# TerminalBlock.net
KiCad netlist of a schematic drawn in Altium Designer
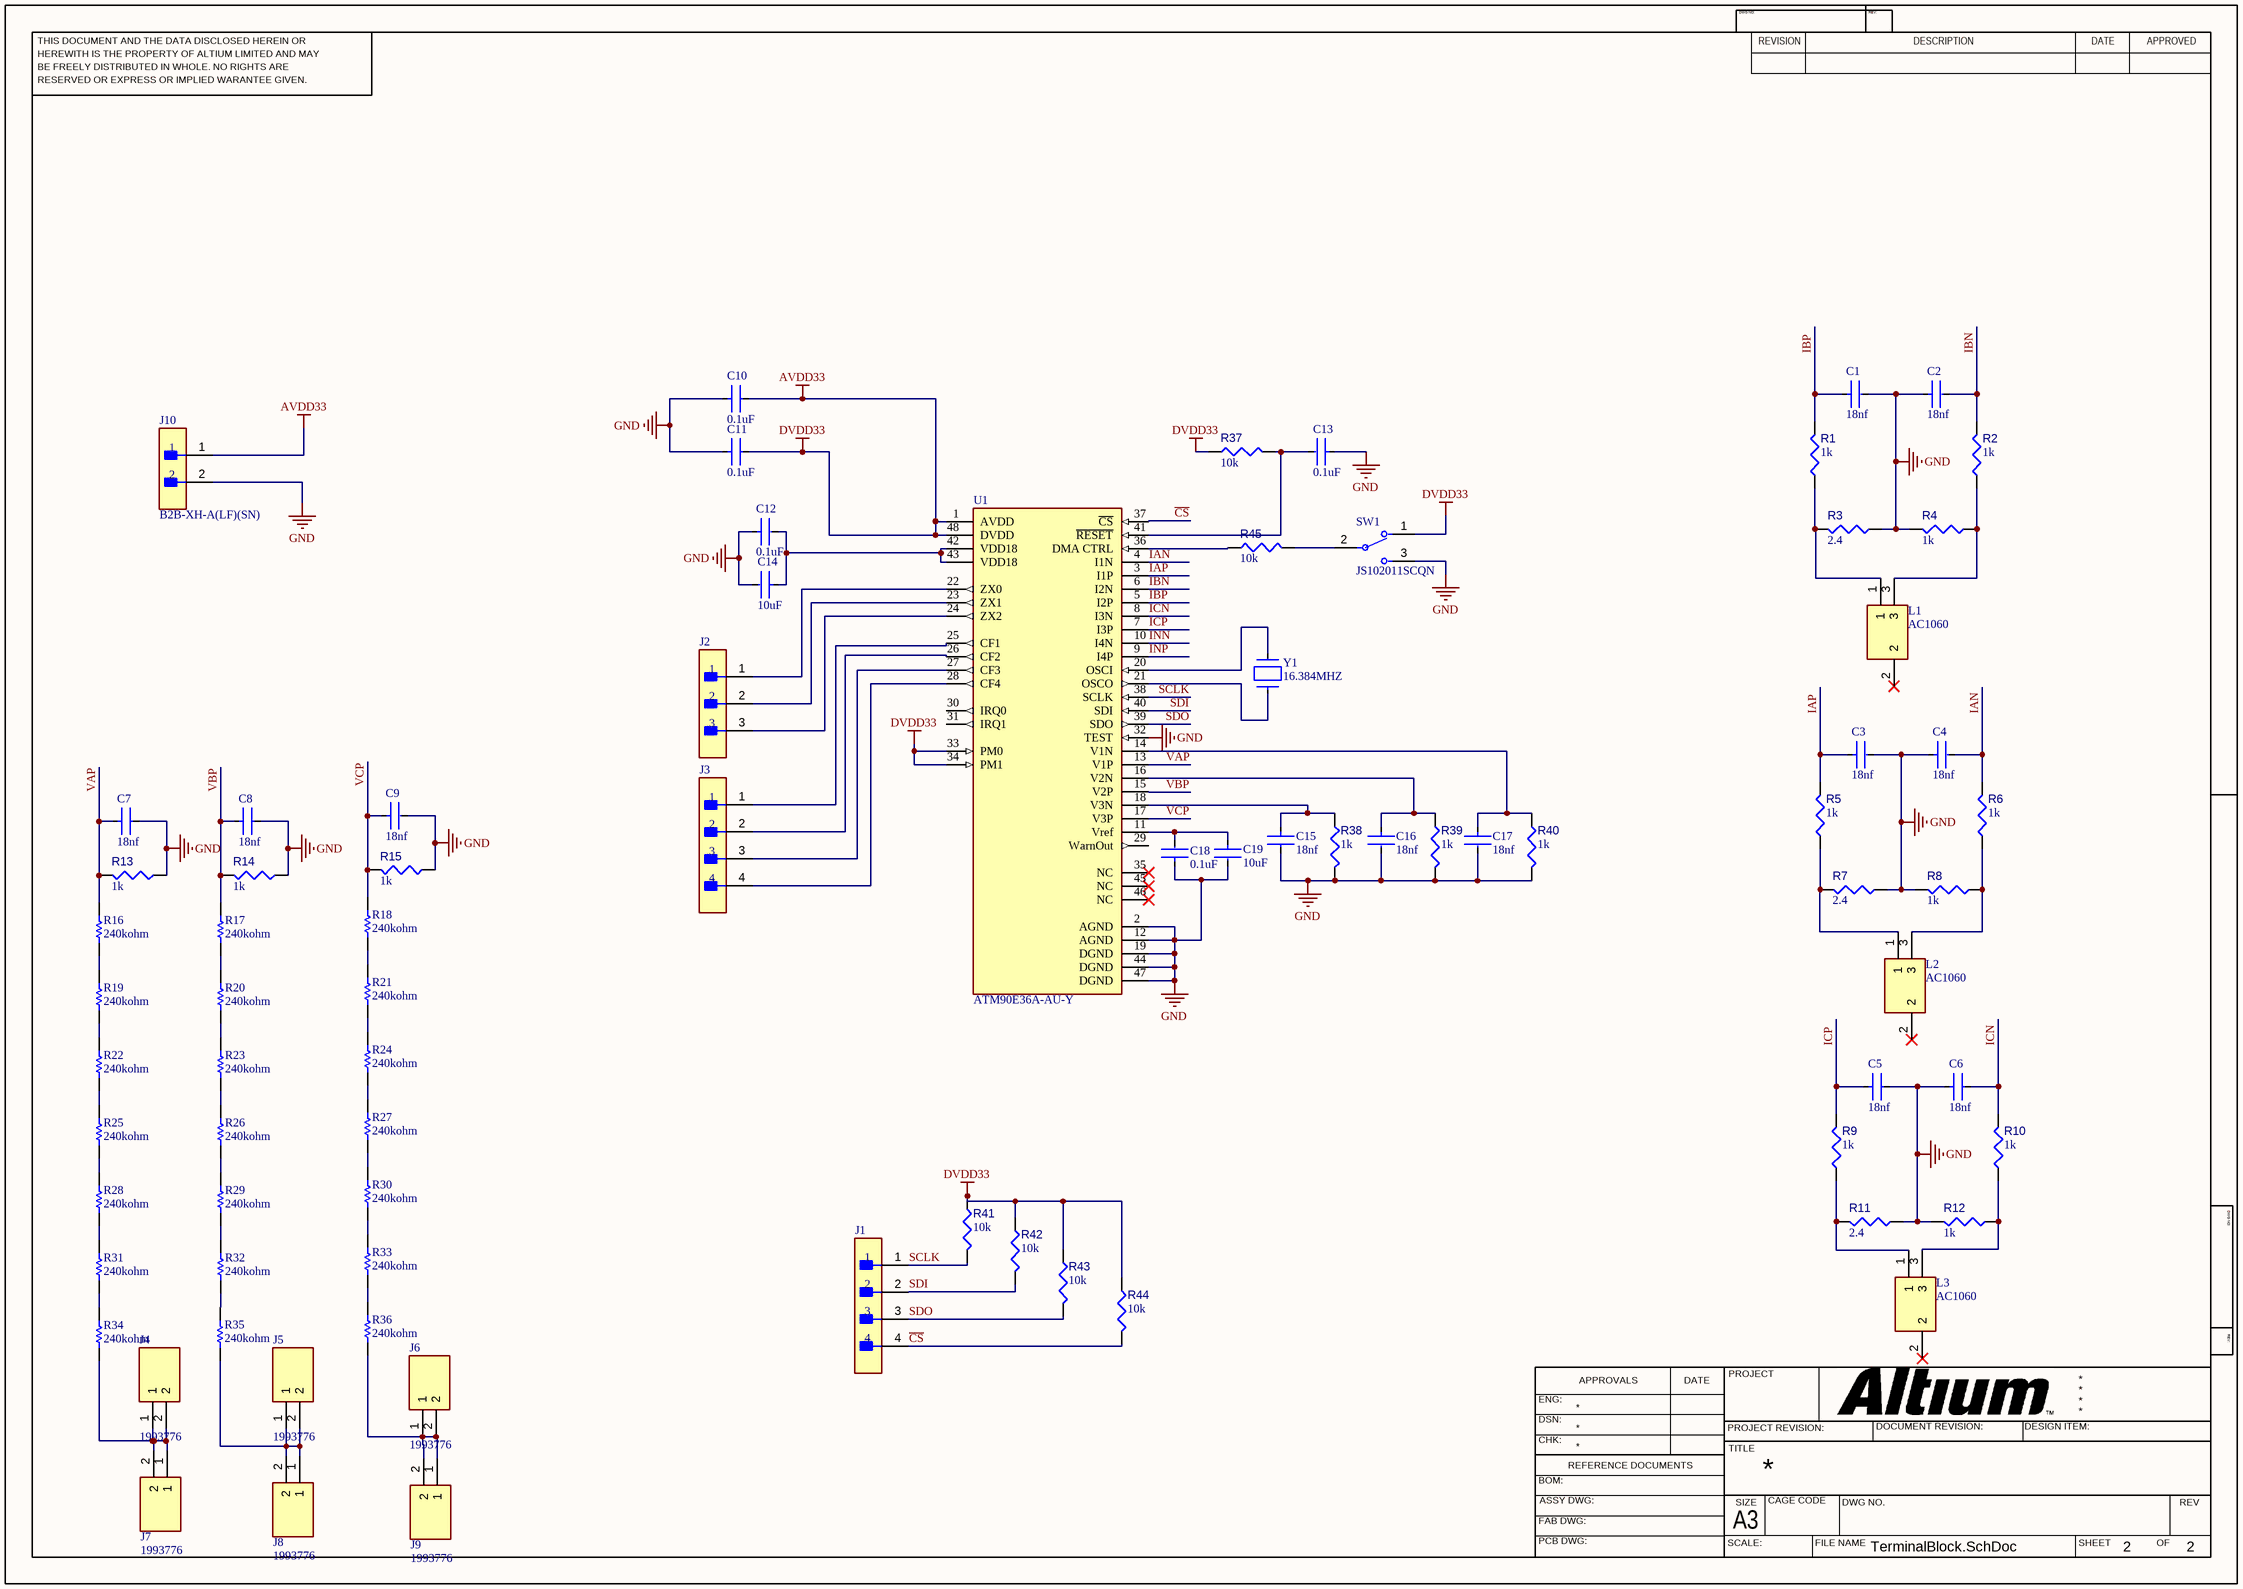
[diagram p0: TerminalBlock.SchDoc]

(export (version "E")
  (design (tool "Eeschema 10.0.6"))
  (components
    (comp (ref "C1")
      (value "18nf")
      (footprint "FP-C0603C-CF-MFG")
      (description "CAP CER 0.018UF 50V 10% X7R 0603")
      (fields
        (field (name "OCTOPART") "https://octopart.com/c0603c183k5ractu-kemet-9138582")
        (field (name "TOLERANCE") "0.1")
      )
      (libsource (lib "Altium Content Vault") (part "b4654b650e69147ec39a6b967a45e02"))
    )
    (comp (ref "C2")
      (value "18nf")
      (footprint "FP-C0603C-CF-MFG")
      (description "CAP CER 0.018UF 50V 10% X7R 0603")
      (fields
        (field (name "OCTOPART") "https://octopart.com/c0603c183k5ractu-kemet-9138582")
        (field (name "TOLERANCE") "0.1")
      )
      (libsource (lib "Altium Content Vault") (part "b4654b650e69147ec39a6b967a45e02"))
    )
    (comp (ref "C3")
      (value "18nf")
      (footprint "FP-C0603C-CF-MFG")
      (description "CAP CER 0.018UF 50V 10% X7R 0603")
      (fields
        (field (name "OCTOPART") "https://octopart.com/c0603c183k5ractu-kemet-9138582")
        (field (name "TOLERANCE") "0.1")
      )
      (libsource (lib "Altium Content Vault") (part "b4654b650e69147ec39a6b967a45e02"))
    )
    (comp (ref "C4")
      (value "18nf")
      (footprint "FP-C0603C-CF-MFG")
      (description "CAP CER 0.018UF 50V 10% X7R 0603")
      (fields
        (field (name "OCTOPART") "https://octopart.com/c0603c183k5ractu-kemet-9138582")
        (field (name "TOLERANCE") "0.1")
      )
      (libsource (lib "Altium Content Vault") (part "b4654b650e69147ec39a6b967a45e02"))
    )
    (comp (ref "C5")
      (value "18nf")
      (footprint "FP-C0603C-CF-MFG")
      (description "CAP CER 0.018UF 50V 10% X7R 0603")
      (fields
        (field (name "OCTOPART") "https://octopart.com/c0603c183k5ractu-kemet-9138582")
        (field (name "TOLERANCE") "0.1")
      )
      (libsource (lib "Altium Content Vault") (part "b4654b650e69147ec39a6b967a45e02"))
    )
    (comp (ref "C6")
      (value "18nf")
      (footprint "FP-C0603C-CF-MFG")
      (description "CAP CER 0.018UF 50V 10% X7R 0603")
      (fields
        (field (name "OCTOPART") "https://octopart.com/c0603c183k5ractu-kemet-9138582")
        (field (name "TOLERANCE") "0.1")
      )
      (libsource (lib "Altium Content Vault") (part "b4654b650e69147ec39a6b967a45e02"))
    )
    (comp (ref "C7")
      (value "18nf")
      (footprint "FP-C0603C-CF-MFG")
      (description "CAP CER 0.018UF 50V 10% X7R 0603")
      (fields
        (field (name "OCTOPART") "https://octopart.com/c0603c183k5ractu-kemet-9138582")
        (field (name "TOLERANCE") "0.1")
      )
      (libsource (lib "Altium Content Vault") (part "b4654b650e69147ec39a6b967a45e02"))
    )
    (comp (ref "C8")
      (value "18nf")
      (footprint "FP-C0603C-CF-MFG")
      (description "CAP CER 0.018UF 50V 10% X7R 0603")
      (fields
        (field (name "OCTOPART") "https://octopart.com/c0603c183k5ractu-kemet-9138582")
        (field (name "TOLERANCE") "0.1")
      )
      (libsource (lib "Altium Content Vault") (part "b4654b650e69147ec39a6b967a45e02"))
    )
    (comp (ref "C9")
      (value "18nf")
      (footprint "FP-C0603C-CF-MFG")
      (description "CAP CER 0.018UF 50V 10% X7R 0603")
      (fields
        (field (name "OCTOPART") "https://octopart.com/c0603c183k5ractu-kemet-9138582")
        (field (name "TOLERANCE") "0.1")
      )
      (libsource (lib "Altium Content Vault") (part "b4654b650e69147ec39a6b967a45e02"))
    )
    (comp (ref "C10")
      (value "0.1uF")
      (footprint "FP-C0603-CJ-MFG")
      (description "CAP CER 0.1UF 50V X7R 0603")
      (fields (field (name "MANUFACTURER PART NUMBER") "C0603X104K5RACTU") (field (name "VOLTAGE") "50V"))
      (libsource (lib "Altium Content Vault") (part "11868f565c42a9108669ba33697ecf6"))
    )
    (comp (ref "C11")
      (value "0.1uF")
      (footprint "FP-C0603-CJ-MFG")
      (description "CAP CER 0.1UF 50V X7R 0603")
      (fields (field (name "MANUFACTURER PART NUMBER") "C0603X104K5RACTU") (field (name "VOLTAGE") "50V"))
      (libsource (lib "Altium Content Vault") (part "11868f565c42a9108669ba33697ecf6"))
    )
    (comp (ref "C12")
      (value "0.1uF")
      (footprint "FP-C0603-CJ-MFG")
      (description "CAP CER 0.1UF 50V X7R 0603")
      (fields (field (name "MANUFACTURER PART NUMBER") "C0603X104K5RACTU") (field (name "VOLTAGE") "50V"))
      (libsource (lib "Altium Content Vault") (part "11868f565c42a9108669ba33697ecf6"))
    )
    (comp (ref "C13")
      (value "0.1uF")
      (footprint "FP-C0603-CJ-MFG")
      (description "CAP CER 0.1UF 50V X7R 0603")
      (fields (field (name "MANUFACTURER PART NUMBER") "C0603X104K5RACTU") (field (name "VOLTAGE") "50V"))
      (libsource (lib "Altium Content Vault") (part "11868f565c42a9108669ba33697ecf6"))
    )
    (comp (ref "C14")
      (value "10uF")
      (footprint "FP-C0603C106M9PACTU-MFG")
      (description "CAP CER 10UF 6.3V X5R 0603")
      (fields
        (field (name "MANUFACTURER PART NUMBER") "C0603C106M9PACTU")
        (field (name "MANUFACTURER") "Kemet")
      )
      (libsource (lib "Altium Content Vault") (part "b4654b650e69147ec39a6b967a45e02"))
    )
    (comp (ref "C15")
      (value "18nf")
      (footprint "FP-C0603C-CF-MFG")
      (description "CAP CER 0.018UF 50V 10% X7R 0603")
      (fields
        (field (name "OCTOPART") "https://octopart.com/c0603c183k5ractu-kemet-9138582")
        (field (name "TOLERANCE") "0.1")
      )
      (libsource (lib "Altium Content Vault") (part "b4654b650e69147ec39a6b967a45e02"))
    )
    (comp (ref "C16")
      (value "18nf")
      (footprint "FP-C0603C-CF-MFG")
      (description "CAP CER 0.018UF 50V 10% X7R 0603")
      (fields
        (field (name "OCTOPART") "https://octopart.com/c0603c183k5ractu-kemet-9138582")
        (field (name "TOLERANCE") "0.1")
      )
      (libsource (lib "Altium Content Vault") (part "b4654b650e69147ec39a6b967a45e02"))
    )
    (comp (ref "C17")
      (value "18nf")
      (footprint "FP-C0603C-CF-MFG")
      (description "CAP CER 0.018UF 50V 10% X7R 0603")
      (fields
        (field (name "OCTOPART") "https://octopart.com/c0603c183k5ractu-kemet-9138582")
        (field (name "TOLERANCE") "0.1")
      )
      (libsource (lib "Altium Content Vault") (part "b4654b650e69147ec39a6b967a45e02"))
    )
    (comp (ref "C18")
      (value "0.1uF")
      (footprint "FP-C0603-CJ-MFG")
      (description "CAP CER 0.1UF 50V X7R 0603")
      (fields (field (name "MANUFACTURER PART NUMBER") "C0603X104K5RACTU") (field (name "VOLTAGE") "50V"))
      (libsource (lib "Altium Content Vault") (part "11868f565c42a9108669ba33697ecf6"))
    )
    (comp (ref "C19")
      (value "10uF")
      (footprint "FP-C0603C106M9PACTU-MFG")
      (description "CAP CER 10UF 6.3V X5R 0603")
      (fields
        (field (name "MANUFACTURER PART NUMBER") "C0603C106M9PACTU")
        (field (name "MANUFACTURER") "Kemet")
      )
      (libsource (lib "Altium Content Vault") (part "b4654b650e69147ec39a6b967a45e02"))
    )
    (comp (ref "J1")
      (value "B4B-XH-A(LF)(SN)")
      (footprint "FP-B4B-XH-A_LF_SN-MFG")
      (description "CONN HEADER VERT 4POS 2.5MM")
      (libsource (lib "Altium Content Vault") (part "299a8cea1bdcbc3624fe62c390fa72c"))
    )
    (comp (ref "J2")
      (value "B3B-XH-A(LF)(SN)")
      (footprint "FP-B3B-XH-A_LF_SN-MFG")
      (description "CONN HEADER VERT 3POS 2.5MM")
      (libsource (lib "Altium Content Vault") (part "0d3f023dd272f625e17a2be33dea85f"))
    )
    (comp (ref "J3")
      (value "B4B-XH-A(LF)(SN)")
      (footprint "FP-B4B-XH-A_LF_SN-MFG")
      (description "CONN HEADER VERT 4POS 2.5MM")
      (libsource (lib "Altium Content Vault") (part "299a8cea1bdcbc3624fe62c390fa72c"))
    )
    (comp (ref "J4")
      (value "1993776")
      (footprint "SamacSys:1993776")
      (description "Connector")
      (fields (field (name "MOUSER PART NUMBER") "651-1993776"))
      (libsource (lib "") (part "1993776_1"))
    )
    (comp (ref "J5")
      (value "1993776")
      (footprint "SamacSys:1993776")
      (description "Connector")
      (fields (field (name "MOUSER PART NUMBER") "651-1993776"))
      (libsource (lib "") (part "1993776_1"))
    )
    (comp (ref "J6")
      (value "1993776")
      (footprint "SamacSys:1993776")
      (description "Connector")
      (fields (field (name "MOUSER PART NUMBER") "651-1993776"))
      (libsource (lib "") (part "1993776_1"))
    )
    (comp (ref "J7")
      (value "1993776")
      (footprint "SamacSys:1993776")
      (description "Connector")
      (fields (field (name "MOUSER PART NUMBER") "651-1993776"))
      (libsource (lib "*") (part "1993776"))
    )
    (comp (ref "J8")
      (value "1993776")
      (footprint "SamacSys:1993776")
      (description "Connector")
      (fields (field (name "MOUSER PART NUMBER") "651-1993776"))
      (libsource (lib "*") (part "1993776"))
    )
    (comp (ref "J9")
      (value "1993776")
      (footprint "SamacSys:1993776")
      (description "Connector")
      (fields (field (name "MOUSER PART NUMBER") "651-1993776"))
      (libsource (lib "*") (part "1993776"))
    )
    (comp (ref "J10")
      (value "B2B-XH-A(LF)(SN)")
      (footprint "FP-B2B-XH-A_LF_SN-MFG")
      (description "CONN HEADER VERT 2POS 2.5MM")
      (libsource (lib "Altium Content Vault") (part "3bc925449376181038e59eaffc5286c"))
    )
    (comp (ref "L1")
      (value "AC1060")
      (footprint "SamacSys:AC1060")
      (description "Inductor")
      (libsource (lib "*") (part "AC1060"))
    )
    (comp (ref "L2")
      (value "AC1060")
      (footprint "SamacSys:AC1060")
      (description "Inductor")
      (libsource (lib "*") (part "AC1060"))
    )
    (comp (ref "L3")
      (value "AC1060")
      (footprint "SamacSys:AC1060")
      (description "Inductor")
      (libsource (lib "*") (part "AC1060"))
    )
    (comp (ref "R1")
      (value "1k")
      (footprint "RESC1608X55X25ML10T15")
      (description "Chip Resistor, 100 KOhm, +/- 1%, 0.1 W, -55 to 155 degC, 0603 (1608 Metric)")
      (fields (field (name "TOLERANCE") "1%") (field (name "POWER") "100mW"))
      (libsource (lib "University of Moratuwa") (part "RES-2"))
    )
    (comp (ref "R2")
      (value "1k")
      (footprint "RESC1608X55X25ML10T15")
      (description "Chip Resistor, 100 KOhm, +/- 1%, 0.1 W, -55 to 155 degC, 0603 (1608 Metric)")
      (fields (field (name "TOLERANCE") "1%") (field (name "POWER") "100mW"))
      (libsource (lib "University of Moratuwa") (part "RES-2"))
    )
    (comp (ref "R3")
      (value "2.4")
      (footprint "RESC1608X55X25ML10T15")
      (description "Chip Resistor, 100 KOhm, +/- 1%, 0.1 W, -55 to 155 degC, 0603 (1608 Metric)")
      (fields (field (name "TOLERANCE") "1%") (field (name "POWER") "100mW"))
      (libsource (lib "University of Moratuwa") (part "RES-2"))
    )
    (comp (ref "R4")
      (value "1k")
      (footprint "RESC1608X55X25ML10T15")
      (description "Chip Resistor, 100 KOhm, +/- 1%, 0.1 W, -55 to 155 degC, 0603 (1608 Metric)")
      (fields (field (name "TOLERANCE") "1%") (field (name "POWER") "100mW"))
      (libsource (lib "University of Moratuwa") (part "RES-2"))
    )
    (comp (ref "R5")
      (value "1k")
      (footprint "RESC1608X55X25ML10T15")
      (description "Chip Resistor, 100 KOhm, +/- 1%, 0.1 W, -55 to 155 degC, 0603 (1608 Metric)")
      (fields (field (name "TOLERANCE") "1%") (field (name "POWER") "100mW"))
      (libsource (lib "University of Moratuwa") (part "RES-2"))
    )
    (comp (ref "R6")
      (value "1k")
      (footprint "RESC1608X55X25ML10T15")
      (description "Chip Resistor, 100 KOhm, +/- 1%, 0.1 W, -55 to 155 degC, 0603 (1608 Metric)")
      (fields (field (name "TOLERANCE") "1%") (field (name "POWER") "100mW"))
      (libsource (lib "University of Moratuwa") (part "RES-2"))
    )
    (comp (ref "R7")
      (value "2.4")
      (footprint "RESC1608X55X25ML10T15")
      (description "Chip Resistor, 100 KOhm, +/- 1%, 0.1 W, -55 to 155 degC, 0603 (1608 Metric)")
      (fields (field (name "TOLERANCE") "1%") (field (name "POWER") "100mW"))
      (libsource (lib "University of Moratuwa") (part "RES-2"))
    )
    (comp (ref "R8")
      (value "1k")
      (footprint "RESC1608X55X25ML10T15")
      (description "Chip Resistor, 100 KOhm, +/- 1%, 0.1 W, -55 to 155 degC, 0603 (1608 Metric)")
      (fields (field (name "TOLERANCE") "1%") (field (name "POWER") "100mW"))
      (libsource (lib "University of Moratuwa") (part "RES-2"))
    )
    (comp (ref "R9")
      (value "1k")
      (footprint "RESC1608X55X25ML10T15")
      (description "Chip Resistor, 100 KOhm, +/- 1%, 0.1 W, -55 to 155 degC, 0603 (1608 Metric)")
      (fields (field (name "TOLERANCE") "1%") (field (name "POWER") "100mW"))
      (libsource (lib "University of Moratuwa") (part "RES-2"))
    )
    (comp (ref "R10")
      (value "1k")
      (footprint "RESC1608X55X25ML10T15")
      (description "Chip Resistor, 100 KOhm, +/- 1%, 0.1 W, -55 to 155 degC, 0603 (1608 Metric)")
      (fields (field (name "TOLERANCE") "1%") (field (name "POWER") "100mW"))
      (libsource (lib "University of Moratuwa") (part "RES-2"))
    )
    (comp (ref "R11")
      (value "2.4")
      (footprint "RESC1608X55X25ML10T15")
      (description "Chip Resistor, 100 KOhm, +/- 1%, 0.1 W, -55 to 155 degC, 0603 (1608 Metric)")
      (fields (field (name "TOLERANCE") "1%") (field (name "POWER") "100mW"))
      (libsource (lib "University of Moratuwa") (part "RES-2"))
    )
    (comp (ref "R12")
      (value "1k")
      (footprint "RESC1608X55X25ML10T15")
      (description "Chip Resistor, 100 KOhm, +/- 1%, 0.1 W, -55 to 155 degC, 0603 (1608 Metric)")
      (fields (field (name "TOLERANCE") "1%") (field (name "POWER") "100mW"))
      (libsource (lib "University of Moratuwa") (part "RES-2"))
    )
    (comp (ref "R13")
      (value "1k")
      (footprint "RESC1608X55X25ML10T15")
      (description "Chip Resistor, 100 KOhm, +/- 1%, 0.1 W, -55 to 155 degC, 0603 (1608 Metric)")
      (fields (field (name "TOLERANCE") "1%") (field (name "POWER") "100mW"))
      (libsource (lib "University of Moratuwa") (part "RES-2"))
    )
    (comp (ref "R14")
      (value "1k")
      (footprint "RESC1608X55X25ML10T15")
      (description "Chip Resistor, 100 KOhm, +/- 1%, 0.1 W, -55 to 155 degC, 0603 (1608 Metric)")
      (fields (field (name "TOLERANCE") "1%") (field (name "POWER") "100mW"))
      (libsource (lib "University of Moratuwa") (part "RES-2"))
    )
    (comp (ref "R15")
      (value "1k")
      (footprint "RESC1608X55X25ML10T15")
      (description "Chip Resistor, 100 KOhm, +/- 1%, 0.1 W, -55 to 155 degC, 0603 (1608 Metric)")
      (fields (field (name "TOLERANCE") "1%") (field (name "POWER") "100mW"))
      (libsource (lib "University of Moratuwa") (part "RES-2"))
    )
    (comp (ref "R16")
      (value "240kohm")
      (footprint "RESC1608X55X30NL20T20")
      (fields (field (name "PART NUMBER") "ERA3AEB244V") (field (name "MANUFACTURER") "Panasonic"))
      (libsource (lib "Altium Content Vault") (part "RES"))
    )
    (comp (ref "R17")
      (value "240kohm")
      (footprint "RESC1608X55X30NL20T20")
      (fields (field (name "PART NUMBER") "ERA3AEB244V") (field (name "MANUFACTURER") "Panasonic"))
      (libsource (lib "Altium Content Vault") (part "RES"))
    )
    (comp (ref "R18")
      (value "240kohm")
      (footprint "RESC1608X55X30NL20T20")
      (fields (field (name "PART NUMBER") "ERA3AEB244V") (field (name "MANUFACTURER") "Panasonic"))
      (libsource (lib "Altium Content Vault") (part "RES"))
    )
    (comp (ref "R19")
      (value "240kohm")
      (footprint "RESC1608X55X30NL20T20")
      (fields (field (name "PART NUMBER") "ERA3AEB244V") (field (name "MANUFACTURER") "Panasonic"))
      (libsource (lib "Altium Content Vault") (part "RES"))
    )
    (comp (ref "R20")
      (value "240kohm")
      (footprint "RESC1608X55X30NL20T20")
      (fields (field (name "PART NUMBER") "ERA3AEB244V") (field (name "MANUFACTURER") "Panasonic"))
      (libsource (lib "Altium Content Vault") (part "RES"))
    )
    (comp (ref "R21")
      (value "240kohm")
      (footprint "RESC1608X55X30NL20T20")
      (fields (field (name "PART NUMBER") "ERA3AEB244V") (field (name "MANUFACTURER") "Panasonic"))
      (libsource (lib "Altium Content Vault") (part "RES"))
    )
    (comp (ref "R22")
      (value "240kohm")
      (footprint "RESC1608X55X30NL20T20")
      (fields (field (name "PART NUMBER") "ERA3AEB244V") (field (name "MANUFACTURER") "Panasonic"))
      (libsource (lib "Altium Content Vault") (part "RES"))
    )
    (comp (ref "R23")
      (value "240kohm")
      (footprint "RESC1608X55X30NL20T20")
      (fields (field (name "PART NUMBER") "ERA3AEB244V") (field (name "MANUFACTURER") "Panasonic"))
      (libsource (lib "Altium Content Vault") (part "RES"))
    )
    (comp (ref "R24")
      (value "240kohm")
      (footprint "RESC1608X55X30NL20T20")
      (fields (field (name "PART NUMBER") "ERA3AEB244V") (field (name "MANUFACTURER") "Panasonic"))
      (libsource (lib "Altium Content Vault") (part "RES"))
    )
    (comp (ref "R25")
      (value "240kohm")
      (footprint "RESC1608X55X30NL20T20")
      (fields (field (name "PART NUMBER") "ERA3AEB244V") (field (name "MANUFACTURER") "Panasonic"))
      (libsource (lib "Altium Content Vault") (part "RES"))
    )
    (comp (ref "R26")
      (value "240kohm")
      (footprint "RESC1608X55X30NL20T20")
      (fields (field (name "PART NUMBER") "ERA3AEB244V") (field (name "MANUFACTURER") "Panasonic"))
      (libsource (lib "Altium Content Vault") (part "RES"))
    )
    (comp (ref "R27")
      (value "240kohm")
      (footprint "RESC1608X55X30NL20T20")
      (fields (field (name "PART NUMBER") "ERA3AEB244V") (field (name "MANUFACTURER") "Panasonic"))
      (libsource (lib "Altium Content Vault") (part "RES"))
    )
    (comp (ref "R28")
      (value "240kohm")
      (footprint "RESC1608X55X30NL20T20")
      (fields (field (name "PART NUMBER") "ERA3AEB244V") (field (name "MANUFACTURER") "Panasonic"))
      (libsource (lib "Altium Content Vault") (part "RES"))
    )
    (comp (ref "R29")
      (value "240kohm")
      (footprint "RESC1608X55X30NL20T20")
      (fields (field (name "PART NUMBER") "ERA3AEB244V") (field (name "MANUFACTURER") "Panasonic"))
      (libsource (lib "Altium Content Vault") (part "RES"))
    )
    (comp (ref "R30")
      (value "240kohm")
      (footprint "RESC1608X55X30NL20T20")
      (fields (field (name "PART NUMBER") "ERA3AEB244V") (field (name "MANUFACTURER") "Panasonic"))
      (libsource (lib "Altium Content Vault") (part "RES"))
    )
    (comp (ref "R31")
      (value "240kohm")
      (footprint "RESC1608X55X30NL20T20")
      (fields (field (name "PART NUMBER") "ERA3AEB244V") (field (name "MANUFACTURER") "Panasonic"))
      (libsource (lib "Altium Content Vault") (part "RES"))
    )
    (comp (ref "R32")
      (value "240kohm")
      (footprint "RESC1608X55X30NL20T20")
      (fields (field (name "PART NUMBER") "ERA3AEB244V") (field (name "MANUFACTURER") "Panasonic"))
      (libsource (lib "Altium Content Vault") (part "RES"))
    )
    (comp (ref "R33")
      (value "240kohm")
      (footprint "RESC1608X55X30NL20T20")
      (fields (field (name "PART NUMBER") "ERA3AEB244V") (field (name "MANUFACTURER") "Panasonic"))
      (libsource (lib "Altium Content Vault") (part "RES"))
    )
    (comp (ref "R34")
      (value "240kohm")
      (footprint "RESC1608X55X30NL20T20")
      (fields (field (name "PART NUMBER") "ERA3AEB244V") (field (name "MANUFACTURER") "Panasonic"))
      (libsource (lib "Altium Content Vault") (part "RES"))
    )
    (comp (ref "R35")
      (value "240kohm")
      (footprint "RESC1608X55X30NL20T20")
      (fields (field (name "PART NUMBER") "ERA3AEB244V") (field (name "MANUFACTURER") "Panasonic"))
      (libsource (lib "Altium Content Vault") (part "RES"))
    )
    (comp (ref "R36")
      (value "240kohm")
      (footprint "RESC1608X55X30NL20T20")
      (fields (field (name "PART NUMBER") "ERA3AEB244V") (field (name "MANUFACTURER") "Panasonic"))
      (libsource (lib "Altium Content Vault") (part "RES"))
    )
    (comp (ref "R37")
      (value "10k")
      (footprint "RESC1608X55X25ML10T15")
      (description "Chip Resistor, 100 KOhm, +/- 1%, 0.1 W, -55 to 155 degC, 0603 (1608 Metric)")
      (fields (field (name "TOLERANCE") "1%") (field (name "POWER") "100mW"))
      (libsource (lib "University of Moratuwa") (part "RES-2"))
    )
    (comp (ref "R38")
      (value "1k")
      (footprint "RESC1608X55X25ML10T15")
      (description "Chip Resistor, 100 KOhm, +/- 1%, 0.1 W, -55 to 155 degC, 0603 (1608 Metric)")
      (fields (field (name "TOLERANCE") "1%") (field (name "POWER") "100mW"))
      (libsource (lib "University of Moratuwa") (part "RES-2"))
    )
    (comp (ref "R39")
      (value "1k")
      (footprint "RESC1608X55X25ML10T15")
      (description "Chip Resistor, 100 KOhm, +/- 1%, 0.1 W, -55 to 155 degC, 0603 (1608 Metric)")
      (fields (field (name "TOLERANCE") "1%") (field (name "POWER") "100mW"))
      (libsource (lib "University of Moratuwa") (part "RES-2"))
    )
    (comp (ref "R40")
      (value "1k")
      (footprint "RESC1608X55X25ML10T15")
      (description "Chip Resistor, 100 KOhm, +/- 1%, 0.1 W, -55 to 155 degC, 0603 (1608 Metric)")
      (fields (field (name "TOLERANCE") "1%") (field (name "POWER") "100mW"))
      (libsource (lib "University of Moratuwa") (part "RES-2"))
    )
    (comp (ref "R41")
      (value "10k")
      (footprint "RESC1608X55X25ML10T15")
      (description "Chip Resistor, 100 KOhm, +/- 1%, 0.1 W, -55 to 155 degC, 0603 (1608 Metric)")
      (fields (field (name "TOLERANCE") "1%") (field (name "POWER") "100mW"))
      (libsource (lib "University of Moratuwa") (part "RES-2"))
    )
    (comp (ref "R42")
      (value "10k")
      (footprint "RESC1608X55X25ML10T15")
      (description "Chip Resistor, 100 KOhm, +/- 1%, 0.1 W, -55 to 155 degC, 0603 (1608 Metric)")
      (fields (field (name "TOLERANCE") "1%") (field (name "POWER") "100mW"))
      (libsource (lib "University of Moratuwa") (part "RES-2"))
    )
    (comp (ref "R43")
      (value "10k")
      (footprint "RESC1608X55X25ML10T15")
      (description "Chip Resistor, 100 KOhm, +/- 1%, 0.1 W, -55 to 155 degC, 0603 (1608 Metric)")
      (fields (field (name "TOLERANCE") "1%") (field (name "POWER") "100mW"))
      (libsource (lib "University of Moratuwa") (part "RES-2"))
    )
    (comp (ref "R44")
      (value "10k")
      (footprint "RESC1608X55X25ML10T15")
      (description "Chip Resistor, 100 KOhm, +/- 1%, 0.1 W, -55 to 155 degC, 0603 (1608 Metric)")
      (fields (field (name "TOLERANCE") "1%") (field (name "POWER") "100mW"))
      (libsource (lib "University of Moratuwa") (part "RES-2"))
    )
    (comp (ref "R45")
      (value "10k")
      (footprint "RESC1608X55X25ML10T15")
      (description "Chip Resistor, 100 KOhm, +/- 1%, 0.1 W, -55 to 155 degC, 0603 (1608 Metric)")
      (fields (field (name "TOLERANCE") "1%") (field (name "POWER") "100mW"))
      (libsource (lib "University of Moratuwa") (part "RES-2"))
    )
    (comp (ref "SW1")
      (value "JS102011SCQN")
      (footprint "FP-JS102011SCQN-MFG")
      (description "SWITCH SLIDE SPDT 300MA 6V")
      (libsource (lib "Altium Content Vault") (part "39e195cbbadc85d1df0d7eb6847d379"))
    )
    (comp (ref "U1")
      (value "ATM90E36A-AU-Y")
      (footprint "FP-ATM90E36A-AU-Y-MFG")
      (description "48-TQFP, IND TEMP, 1.8V/3V, TRAY")
      (libsource (lib "Altium Content Vault") (part "6bafd089a959a04736d12024ed6fd38"))
    )
    (comp (ref "Y1")
      (value "16.384MHZ")
      (footprint "FP-ABM2-MFG")
      (description "Crystal 16.384MHz ±30ppm 18pF SMD-2 8mm x 4.5mm")
      (fields (field (name "TOLERANCE") "30ppm"))
      (libsource (lib "Altium Content Vault") (part "c23a69dc6c9e2f18f2079038eb95dd1"))
    )
  )
  (nets
    (net (code "1") (name "/IAN") (class "Default")
      (node (ref "C4") (pin "2") (pinfunction "2_2") (pintype "passive"))
      (node (ref "R6") (pin "2") (pinfunction "2_2") (pintype "passive"))
      (node (ref "U1") (pin "4") (pinfunction "I1N_4") (pintype "passive"))
    )
    (net (code "2") (name "/IAP") (class "Default")
      (node (ref "C3") (pin "1") (pinfunction "1_1") (pintype "passive"))
      (node (ref "R5") (pin "2") (pinfunction "2_2") (pintype "passive"))
      (node (ref "U1") (pin "3") (pinfunction "I1P_3") (pintype "passive"))
    )
    (net (code "3") (name "/IBN") (class "Default")
      (node (ref "C2") (pin "2") (pinfunction "2_2") (pintype "passive"))
      (node (ref "R2") (pin "2") (pinfunction "2_2") (pintype "passive"))
      (node (ref "U1") (pin "6") (pinfunction "I2N_6") (pintype "passive"))
    )
    (net (code "4") (name "/IBP") (class "Default")
      (node (ref "C1") (pin "1") (pinfunction "1_1") (pintype "passive"))
      (node (ref "R1") (pin "2") (pinfunction "2_2") (pintype "passive"))
      (node (ref "U1") (pin "5") (pinfunction "I2P_5") (pintype "passive"))
    )
    (net (code "5") (name "/ICN") (class "Default")
      (node (ref "C6") (pin "2") (pinfunction "2_2") (pintype "passive"))
      (node (ref "R10") (pin "2") (pinfunction "2_2") (pintype "passive"))
      (node (ref "U1") (pin "8") (pinfunction "I3N_8") (pintype "passive"))
    )
    (net (code "6") (name "/ICP") (class "Default")
      (node (ref "C5") (pin "1") (pinfunction "1_1") (pintype "passive"))
      (node (ref "R9") (pin "2") (pinfunction "2_2") (pintype "passive"))
      (node (ref "U1") (pin "7") (pinfunction "I3P_7") (pintype "passive"))
    )
    (net (code "7") (name "/INN") (class "Default")
      (node (ref "U1") (pin "10") (pinfunction "I4N_10") (pintype "passive"))
    )
    (net (code "8") (name "/INP") (class "Default")
      (node (ref "U1") (pin "9") (pinfunction "I4P_9") (pintype "passive"))
    )
    (net (code "9") (name "/SCLK") (class "Default")
      (node (ref "J1") (pin "1") (pinfunction "1_1") (pintype "passive"))
      (node (ref "R41") (pin "1") (pinfunction "1_1") (pintype "passive"))
      (node (ref "U1") (pin "38") (pinfunction "SCLK_38") (pintype "input"))
    )
    (net (code "10") (name "/SDI") (class "Default")
      (node (ref "J1") (pin "2") (pinfunction "2_2") (pintype "passive"))
      (node (ref "R42") (pin "1") (pinfunction "1_1") (pintype "passive"))
      (node (ref "U1") (pin "40") (pinfunction "SDI_40") (pintype "input"))
    )
    (net (code "11") (name "/SDO") (class "Default")
      (node (ref "J1") (pin "3") (pinfunction "3_3") (pintype "passive"))
      (node (ref "R43") (pin "1") (pinfunction "1_1") (pintype "passive"))
      (node (ref "U1") (pin "39") (pinfunction "SDO_39") (pintype "output"))
    )
    (net (code "12") (name "/VAP") (class "Default")
      (node (ref "C7") (pin "1") (pinfunction "1_1") (pintype "passive"))
      (node (ref "R13") (pin "2") (pinfunction "2_2") (pintype "passive"))
      (node (ref "R16") (pin "2") (pinfunction "2_2") (pintype "passive"))
      (node (ref "U1") (pin "13") (pinfunction "V1P_13") (pintype "passive"))
    )
    (net (code "13") (name "/VBP") (class "Default")
      (node (ref "C8") (pin "1") (pinfunction "1_1") (pintype "passive"))
      (node (ref "R14") (pin "2") (pinfunction "2_2") (pintype "passive"))
      (node (ref "R17") (pin "2") (pinfunction "2_2") (pintype "passive"))
      (node (ref "U1") (pin "15") (pinfunction "V2P_15") (pintype "passive"))
    )
    (net (code "14") (name "/VCP") (class "Default")
      (node (ref "C9") (pin "1") (pinfunction "1_1") (pintype "passive"))
      (node (ref "R15") (pin "2") (pinfunction "2_2") (pintype "passive"))
      (node (ref "R18") (pin "2") (pinfunction "2_2") (pintype "passive"))
      (node (ref "U1") (pin "17") (pinfunction "V3P_17") (pintype "passive"))
    )
    (net (code "15") (name "/~{CS}") (class "Default")
      (node (ref "J1") (pin "4") (pinfunction "4_4") (pintype "passive"))
      (node (ref "R44") (pin "1") (pinfunction "1_1") (pintype "passive"))
      (node (ref "U1") (pin "37") (pinfunction "~{CS}_37") (pintype "input"))
    )
    (net (code "16") (name "AVDD33") (class "Default")
      (node (ref "C10") (pin "2") (pinfunction "2_2") (pintype "passive"))
      (node (ref "C11") (pin "2") (pinfunction "2_2") (pintype "passive"))
      (node (ref "J10") (pin "1") (pinfunction "1_1") (pintype "passive"))
      (node (ref "R37") (pin "2") (pinfunction "2_2") (pintype "passive"))
      (node (ref "R41") (pin "2") (pinfunction "2_2") (pintype "passive"))
      (node (ref "R42") (pin "2") (pinfunction "2_2") (pintype "passive"))
      (node (ref "R43") (pin "2") (pinfunction "2_2") (pintype "passive"))
      (node (ref "R44") (pin "2") (pinfunction "2_2") (pintype "passive"))
      (node (ref "SW1") (pin "1") (pinfunction "1_1") (pintype "passive"))
      (node (ref "U1") (pin "1") (pinfunction "AVDD_1") (pintype "power_in"))
      (node (ref "U1") (pin "33") (pinfunction "PM0_33") (pintype "input"))
      (node (ref "U1") (pin "34") (pinfunction "PM1_34") (pintype "input"))
      (node (ref "U1") (pin "48") (pinfunction "DVDD_48") (pintype "power_in"))
    )
    (net (code "17") (name "GND") (class "Default")
      (node (ref "C1") (pin "2") (pinfunction "2_2") (pintype "passive"))
      (node (ref "C10") (pin "1") (pinfunction "1_1") (pintype "passive"))
      (node (ref "C11") (pin "1") (pinfunction "1_1") (pintype "passive"))
      (node (ref "C12") (pin "1") (pinfunction "1_1") (pintype "passive"))
      (node (ref "C13") (pin "1") (pinfunction "1_1") (pintype "passive"))
      (node (ref "C14") (pin "2") (pinfunction "2_2") (pintype "passive"))
      (node (ref "C15") (pin "2") (pinfunction "2_2") (pintype "passive"))
      (node (ref "C16") (pin "2") (pinfunction "2_2") (pintype "passive"))
      (node (ref "C17") (pin "2") (pinfunction "2_2") (pintype "passive"))
      (node (ref "C18") (pin "1") (pinfunction "1_1") (pintype "passive"))
      (node (ref "C19") (pin "2") (pinfunction "2_2") (pintype "passive"))
      (node (ref "C2") (pin "1") (pinfunction "1_1") (pintype "passive"))
      (node (ref "C3") (pin "2") (pinfunction "2_2") (pintype "passive"))
      (node (ref "C4") (pin "1") (pinfunction "1_1") (pintype "passive"))
      (node (ref "C5") (pin "2") (pinfunction "2_2") (pintype "passive"))
      (node (ref "C6") (pin "1") (pinfunction "1_1") (pintype "passive"))
      (node (ref "C7") (pin "2") (pinfunction "2_2") (pintype "passive"))
      (node (ref "C8") (pin "2") (pinfunction "2_2") (pintype "passive"))
      (node (ref "C9") (pin "2") (pinfunction "2_2") (pintype "passive"))
      (node (ref "J10") (pin "2") (pinfunction "2_2") (pintype "passive"))
      (node (ref "R11") (pin "1") (pinfunction "1_1") (pintype "passive"))
      (node (ref "R12") (pin "2") (pinfunction "2_2") (pintype "passive"))
      (node (ref "R13") (pin "1") (pinfunction "1_1") (pintype "passive"))
      (node (ref "R14") (pin "1") (pinfunction "1_1") (pintype "passive"))
      (node (ref "R15") (pin "1") (pinfunction "1_1") (pintype "passive"))
      (node (ref "R3") (pin "1") (pinfunction "1_1") (pintype "passive"))
      (node (ref "R38") (pin "1") (pinfunction "1_1") (pintype "passive"))
      (node (ref "R39") (pin "1") (pinfunction "1_1") (pintype "passive"))
      (node (ref "R4") (pin "2") (pinfunction "2_2") (pintype "passive"))
      (node (ref "R40") (pin "1") (pinfunction "1_1") (pintype "passive"))
      (node (ref "R7") (pin "1") (pinfunction "1_1") (pintype "passive"))
      (node (ref "R8") (pin "2") (pinfunction "2_2") (pintype "passive"))
      (node (ref "SW1") (pin "3") (pinfunction "3_3") (pintype "passive"))
      (node (ref "U1") (pin "12") (pinfunction "AGND_12") (pintype "power_in"))
      (node (ref "U1") (pin "19") (pinfunction "DGND_19") (pintype "power_in"))
      (node (ref "U1") (pin "2") (pinfunction "AGND_2") (pintype "power_in"))
      (node (ref "U1") (pin "32") (pinfunction "TEST_32") (pintype "input"))
      (node (ref "U1") (pin "44") (pinfunction "DGND_44") (pintype "power_in"))
      (node (ref "U1") (pin "47") (pinfunction "DGND_47") (pintype "power_in"))
    )
    (net (code "18") (name "Net-(C12-Pad2)") (class "Default")
      (node (ref "C12") (pin "2") (pinfunction "2_2") (pintype "passive"))
      (node (ref "C14") (pin "1") (pinfunction "1_1") (pintype "passive"))
      (node (ref "U1") (pin "42") (pinfunction "VDD18_42") (pintype "power_in"))
      (node (ref "U1") (pin "43") (pinfunction "VDD18_43") (pintype "power_in"))
    )
    (net (code "19") (name "Net-(J4-Pad1)") (class "Default")
      (node (ref "J4") (pin "1") (pinfunction "1_1") (pintype "passive"))
      (node (ref "J4") (pin "2") (pinfunction "2_2") (pintype "passive"))
      (node (ref "J7") (pin "1") (pinfunction "1_1") (pintype "passive"))
      (node (ref "J7") (pin "2") (pinfunction "2_2") (pintype "passive"))
      (node (ref "R34") (pin "1") (pinfunction "1_1") (pintype "passive"))
    )
    (net (code "20") (name "Net-(J5-Pad1)") (class "Default")
      (node (ref "J5") (pin "1") (pinfunction "1_1") (pintype "passive"))
      (node (ref "J5") (pin "2") (pinfunction "2_2") (pintype "passive"))
      (node (ref "J8") (pin "1") (pinfunction "1_1") (pintype "passive"))
      (node (ref "J8") (pin "2") (pinfunction "2_2") (pintype "passive"))
      (node (ref "R35") (pin "1") (pinfunction "1_1") (pintype "passive"))
    )
    (net (code "21") (name "Net-(J6-Pad1)") (class "Default")
      (node (ref "J6") (pin "1") (pinfunction "1_1") (pintype "passive"))
      (node (ref "J6") (pin "2") (pinfunction "2_2") (pintype "passive"))
      (node (ref "J9") (pin "1") (pinfunction "1_1") (pintype "passive"))
      (node (ref "J9") (pin "2") (pinfunction "2_2") (pintype "passive"))
      (node (ref "R36") (pin "1") (pinfunction "1_1") (pintype "passive"))
    )
    (net (code "22") (name "Net-(L1-Pad1)") (class "Default")
      (node (ref "L1") (pin "1") (pinfunction "1_1") (pintype "passive"))
      (node (ref "R1") (pin "1") (pinfunction "1_1") (pintype "passive"))
      (node (ref "R3") (pin "2") (pinfunction "2_2") (pintype "passive"))
    )
    (net (code "23") (name "Net-(L1-Pad3)") (class "Default")
      (node (ref "L1") (pin "3") (pinfunction "3_3") (pintype "passive"))
      (node (ref "R2") (pin "1") (pinfunction "1_1") (pintype "passive"))
      (node (ref "R4") (pin "1") (pinfunction "1_1") (pintype "passive"))
    )
    (net (code "24") (name "Net-(L2-Pad1)") (class "Default")
      (node (ref "L2") (pin "1") (pinfunction "1_1") (pintype "passive"))
      (node (ref "R5") (pin "1") (pinfunction "1_1") (pintype "passive"))
      (node (ref "R7") (pin "2") (pinfunction "2_2") (pintype "passive"))
    )
    (net (code "25") (name "Net-(L2-Pad3)") (class "Default")
      (node (ref "L2") (pin "3") (pinfunction "3_3") (pintype "passive"))
      (node (ref "R6") (pin "1") (pinfunction "1_1") (pintype "passive"))
      (node (ref "R8") (pin "1") (pinfunction "1_1") (pintype "passive"))
    )
    (net (code "26") (name "Net-(L3-Pad1)") (class "Default")
      (node (ref "L3") (pin "1") (pinfunction "1_1") (pintype "passive"))
      (node (ref "R11") (pin "2") (pinfunction "2_2") (pintype "passive"))
      (node (ref "R9") (pin "1") (pinfunction "1_1") (pintype "passive"))
    )
    (net (code "27") (name "Net-(L3-Pad3)") (class "Default")
      (node (ref "L3") (pin "3") (pinfunction "3_3") (pintype "passive"))
      (node (ref "R10") (pin "1") (pinfunction "1_1") (pintype "passive"))
      (node (ref "R12") (pin "1") (pinfunction "1_1") (pintype "passive"))
    )
    (net (code "28") (name "Net-(R16-Pad1)") (class "Default")
      (node (ref "R16") (pin "1") (pinfunction "1_1") (pintype "passive"))
      (node (ref "R19") (pin "2") (pinfunction "2_2") (pintype "passive"))
    )
    (net (code "29") (name "Net-(R17-Pad1)") (class "Default")
      (node (ref "R17") (pin "1") (pinfunction "1_1") (pintype "passive"))
      (node (ref "R20") (pin "2") (pinfunction "2_2") (pintype "passive"))
    )
    (net (code "30") (name "Net-(R18-Pad1)") (class "Default")
      (node (ref "R18") (pin "1") (pinfunction "1_1") (pintype "passive"))
      (node (ref "R21") (pin "2") (pinfunction "2_2") (pintype "passive"))
    )
    (net (code "31") (name "Net-(R19-Pad1)") (class "Default")
      (node (ref "R19") (pin "1") (pinfunction "1_1") (pintype "passive"))
      (node (ref "R22") (pin "2") (pinfunction "2_2") (pintype "passive"))
    )
    (net (code "32") (name "Net-(R20-Pad1)") (class "Default")
      (node (ref "R20") (pin "1") (pinfunction "1_1") (pintype "passive"))
      (node (ref "R23") (pin "2") (pinfunction "2_2") (pintype "passive"))
    )
    (net (code "33") (name "Net-(R21-Pad1)") (class "Default")
      (node (ref "R21") (pin "1") (pinfunction "1_1") (pintype "passive"))
      (node (ref "R24") (pin "2") (pinfunction "2_2") (pintype "passive"))
    )
    (net (code "34") (name "Net-(R22-Pad1)") (class "Default")
      (node (ref "R22") (pin "1") (pinfunction "1_1") (pintype "passive"))
      (node (ref "R25") (pin "2") (pinfunction "2_2") (pintype "passive"))
    )
    (net (code "35") (name "Net-(R23-Pad1)") (class "Default")
      (node (ref "R23") (pin "1") (pinfunction "1_1") (pintype "passive"))
      (node (ref "R26") (pin "2") (pinfunction "2_2") (pintype "passive"))
    )
    (net (code "36") (name "Net-(R24-Pad1)") (class "Default")
      (node (ref "R24") (pin "1") (pinfunction "1_1") (pintype "passive"))
      (node (ref "R27") (pin "2") (pinfunction "2_2") (pintype "passive"))
    )
    (net (code "37") (name "Net-(R25-Pad1)") (class "Default")
      (node (ref "R25") (pin "1") (pinfunction "1_1") (pintype "passive"))
      (node (ref "R28") (pin "2") (pinfunction "2_2") (pintype "passive"))
    )
    (net (code "38") (name "Net-(R26-Pad1)") (class "Default")
      (node (ref "R26") (pin "1") (pinfunction "1_1") (pintype "passive"))
      (node (ref "R29") (pin "2") (pinfunction "2_2") (pintype "passive"))
    )
    (net (code "39") (name "Net-(R27-Pad1)") (class "Default")
      (node (ref "R27") (pin "1") (pinfunction "1_1") (pintype "passive"))
      (node (ref "R30") (pin "2") (pinfunction "2_2") (pintype "passive"))
    )
    (net (code "40") (name "Net-(R28-Pad1)") (class "Default")
      (node (ref "R28") (pin "1") (pinfunction "1_1") (pintype "passive"))
      (node (ref "R31") (pin "2") (pinfunction "2_2") (pintype "passive"))
    )
    (net (code "41") (name "Net-(R29-Pad1)") (class "Default")
      (node (ref "R29") (pin "1") (pinfunction "1_1") (pintype "passive"))
      (node (ref "R32") (pin "2") (pinfunction "2_2") (pintype "passive"))
    )
    (net (code "42") (name "Net-(R30-Pad1)") (class "Default")
      (node (ref "R30") (pin "1") (pinfunction "1_1") (pintype "passive"))
      (node (ref "R33") (pin "2") (pinfunction "2_2") (pintype "passive"))
    )
    (net (code "43") (name "Net-(R31-Pad1)") (class "Default")
      (node (ref "R31") (pin "1") (pinfunction "1_1") (pintype "passive"))
      (node (ref "R34") (pin "2") (pinfunction "2_2") (pintype "passive"))
    )
    (net (code "44") (name "Net-(R32-Pad1)") (class "Default")
      (node (ref "R32") (pin "1") (pinfunction "1_1") (pintype "passive"))
      (node (ref "R35") (pin "2") (pinfunction "2_2") (pintype "passive"))
    )
    (net (code "45") (name "Net-(R33-Pad1)") (class "Default")
      (node (ref "R33") (pin "1") (pinfunction "1_1") (pintype "passive"))
      (node (ref "R36") (pin "2") (pinfunction "2_2") (pintype "passive"))
    )
    (net (code "46") (name "Net-(SW1-C)") (class "Default")
      (node (ref "R45") (pin "1") (pinfunction "1_1") (pintype "passive"))
      (node (ref "SW1") (pin "2") (pinfunction "C_2") (pintype "passive"))
    )
    (net (code "47") (name "Net-(U1-CF1)") (class "Default")
      (node (ref "J3") (pin "1") (pinfunction "1_1") (pintype "passive"))
      (node (ref "U1") (pin "25") (pinfunction "CF1_25") (pintype "output"))
    )
    (net (code "48") (name "Net-(U1-CF2)") (class "Default")
      (node (ref "J3") (pin "2") (pinfunction "2_2") (pintype "passive"))
      (node (ref "U1") (pin "26") (pinfunction "CF2_26") (pintype "output"))
    )
    (net (code "49") (name "Net-(U1-CF3)") (class "Default")
      (node (ref "J3") (pin "3") (pinfunction "3_3") (pintype "passive"))
      (node (ref "U1") (pin "27") (pinfunction "CF3_27") (pintype "output"))
    )
    (net (code "50") (name "Net-(U1-CF4)") (class "Default")
      (node (ref "J3") (pin "4") (pinfunction "4_4") (pintype "passive"))
      (node (ref "U1") (pin "28") (pinfunction "CF4_28") (pintype "output"))
    )
    (net (code "51") (name "Net-(U1-DMA_CTRL)") (class "Default")
      (node (ref "R45") (pin "2") (pinfunction "2_2") (pintype "passive"))
      (node (ref "U1") (pin "36") (pinfunction "DMA_CTRL_36") (pintype "input"))
    )
    (net (code "52") (name "Net-(U1-OSCI)") (class "Default")
      (node (ref "U1") (pin "20") (pinfunction "OSCI_20") (pintype "input"))
      (node (ref "Y1") (pin "2") (pinfunction "2_2") (pintype "passive"))
    )
    (net (code "53") (name "Net-(U1-OSCO)") (class "Default")
      (node (ref "U1") (pin "21") (pinfunction "OSCO_21") (pintype "output"))
      (node (ref "Y1") (pin "1") (pinfunction "1_1") (pintype "passive"))
    )
    (net (code "54") (name "Net-(U1-V1N)") (class "Default")
      (node (ref "C17") (pin "1") (pinfunction "1_1") (pintype "passive"))
      (node (ref "R40") (pin "2") (pinfunction "2_2") (pintype "passive"))
      (node (ref "U1") (pin "14") (pinfunction "V1N_14") (pintype "passive"))
    )
    (net (code "55") (name "Net-(U1-V2N)") (class "Default")
      (node (ref "C16") (pin "1") (pinfunction "1_1") (pintype "passive"))
      (node (ref "R39") (pin "2") (pinfunction "2_2") (pintype "passive"))
      (node (ref "U1") (pin "16") (pinfunction "V2N_16") (pintype "passive"))
    )
    (net (code "56") (name "Net-(U1-V3N)") (class "Default")
      (node (ref "C15") (pin "1") (pinfunction "1_1") (pintype "passive"))
      (node (ref "R38") (pin "2") (pinfunction "2_2") (pintype "passive"))
      (node (ref "U1") (pin "18") (pinfunction "V3N_18") (pintype "passive"))
    )
    (net (code "57") (name "Net-(U1-Vref)") (class "Default")
      (node (ref "C18") (pin "2") (pinfunction "2_2") (pintype "passive"))
      (node (ref "C19") (pin "1") (pinfunction "1_1") (pintype "passive"))
      (node (ref "U1") (pin "11") (pinfunction "Vref_11") (pintype "power_in"))
    )
    (net (code "58") (name "Net-(U1-ZX0)") (class "Default")
      (node (ref "J2") (pin "1") (pinfunction "1_1") (pintype "passive"))
      (node (ref "U1") (pin "22") (pinfunction "ZX0_22") (pintype "output"))
    )
    (net (code "59") (name "Net-(U1-ZX1)") (class "Default")
      (node (ref "J2") (pin "2") (pinfunction "2_2") (pintype "passive"))
      (node (ref "U1") (pin "23") (pinfunction "ZX1_23") (pintype "output"))
    )
    (net (code "60") (name "Net-(U1-ZX2)") (class "Default")
      (node (ref "J2") (pin "3") (pinfunction "3_3") (pintype "passive"))
      (node (ref "U1") (pin "24") (pinfunction "ZX2_24") (pintype "output"))
    )
    (net (code "61") (name "Net-(U1-~{RESET})") (class "Default")
      (node (ref "C13") (pin "2") (pinfunction "2_2") (pintype "passive"))
      (node (ref "R37") (pin "1") (pinfunction "1_1") (pintype "passive"))
      (node (ref "U1") (pin "41") (pinfunction "~{RESET}_41") (pintype "input"))
    )
    (net (code "62") (name "unconnected-(L1-Pad2)") (class "Default")
      (node (ref "L1") (pin "2") (pinfunction "2_2") (pintype "passive+no_connect"))
    )
    (net (code "63") (name "unconnected-(L2-Pad2)") (class "Default")
      (node (ref "L2") (pin "2") (pinfunction "2_2") (pintype "passive+no_connect"))
    )
    (net (code "64") (name "unconnected-(L3-Pad2)") (class "Default")
      (node (ref "L3") (pin "2") (pinfunction "2_2") (pintype "passive+no_connect"))
    )
    (net (code "65") (name "unconnected-(U1-IRQ0-Pad30)") (class "Default")
      (node (ref "U1") (pin "30") (pinfunction "IRQ0_30") (pintype "output"))
    )
    (net (code "66") (name "unconnected-(U1-IRQ1-Pad31)") (class "Default")
      (node (ref "U1") (pin "31") (pinfunction "IRQ1_31") (pintype "output"))
    )
    (net (code "67") (name "unconnected-(U1-NC-Pad35)") (class "Default")
      (node (ref "U1") (pin "35") (pinfunction "NC_35") (pintype "passive+no_connect"))
    )
    (net (code "68") (name "unconnected-(U1-NC-Pad45)") (class "Default")
      (node (ref "U1") (pin "45") (pinfunction "NC_45") (pintype "passive+no_connect"))
    )
    (net (code "69") (name "unconnected-(U1-NC-Pad46)") (class "Default")
      (node (ref "U1") (pin "46") (pinfunction "NC_46") (pintype "passive+no_connect"))
    )
    (net (code "70") (name "unconnected-(U1-WarnOut-Pad29)") (class "Default")
      (node (ref "U1") (pin "29") (pinfunction "WarnOut_29") (pintype "output"))
    )
  )
)
